# PROC099A_LDO.net
KiCad netlist of a schematic drawn in Altium Designer
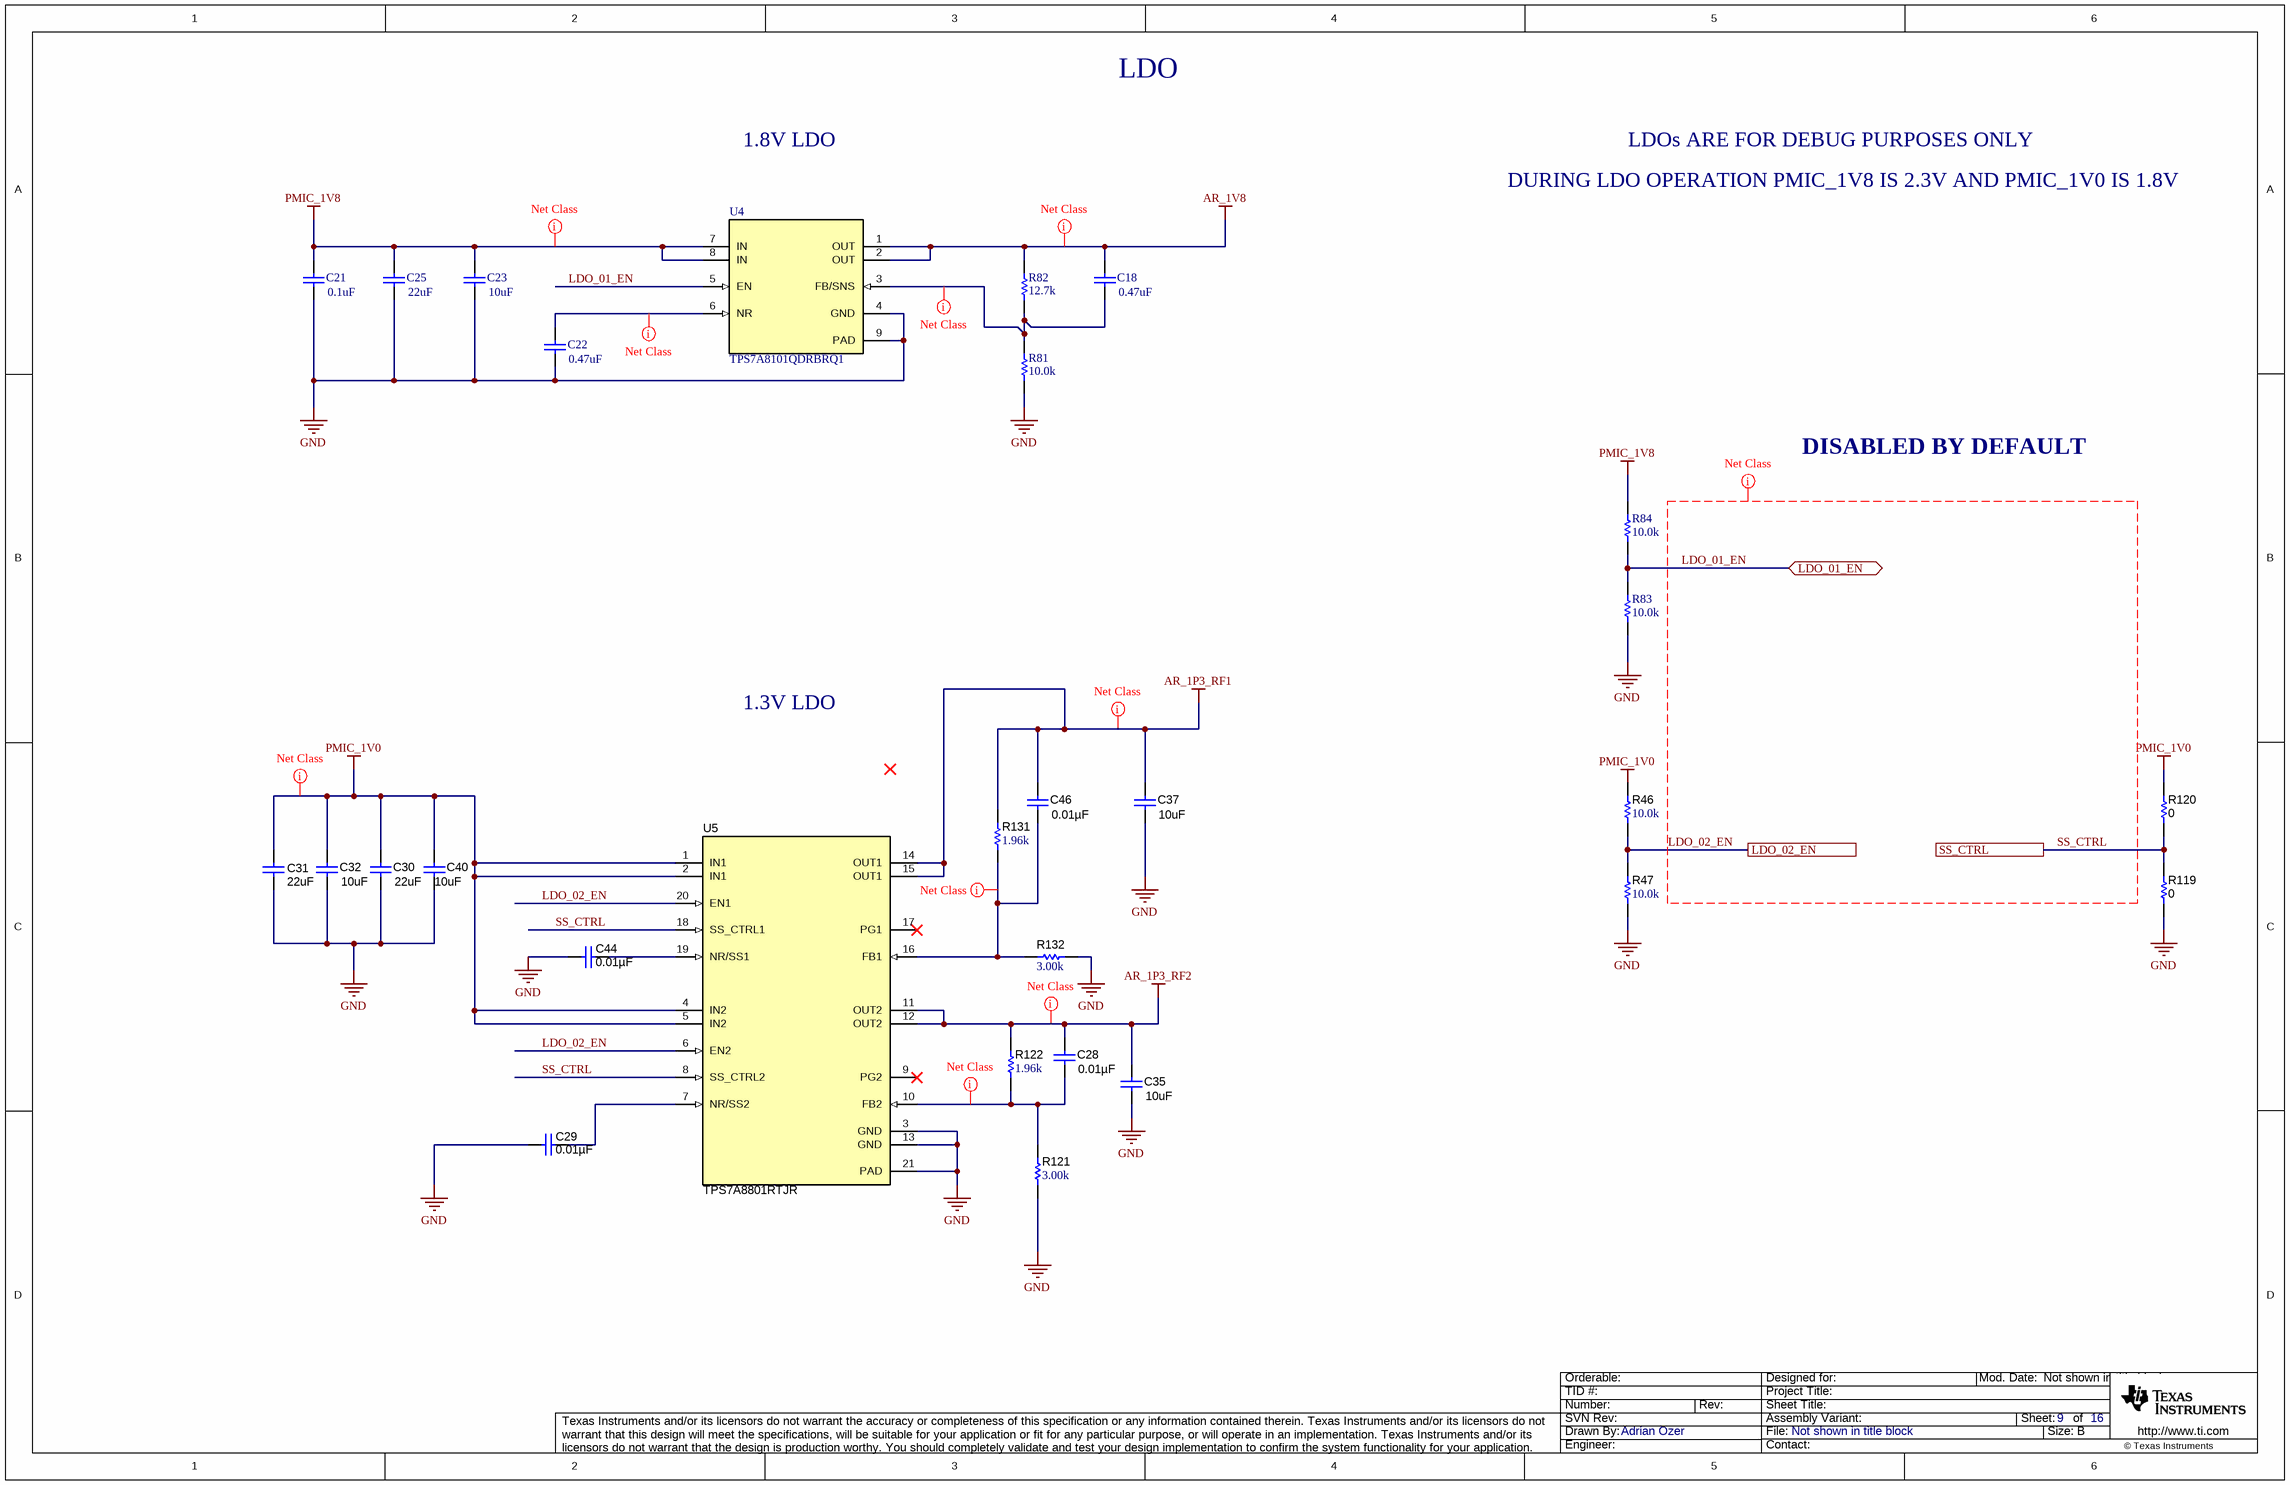
[diagram p0: PROC099A_LDO.SchDoc]

(export (version "E")
  (design (tool "Eeschema 10.0.6"))
  (components
    (comp (ref "C18")
      (value "GCM188R71C474KA55D")
      (footprint "0603")
      (description "CAP, CERM, 0.47 uF, 16 V, +/- 10%, X7R, AEC-Q200 Grade 1, 0603")
      (fields
        (field (name "MANUFACTURER") "MuRata")
        (field (name "VALUEDISPLAYED") "0.47uF")
        (field (name "PUBLISHER") "Texas Instruments")
      )
      (libsource (lib "Altium Vault - TI") (part "Capacitor"))
    )
    (comp (ref "C21")
      (value "CGA2B3X7R1H104K050BB")
      (footprint "0402")
      (description "CAP, CERM, 0.1 uF, 50 V, +/- 10%, X7R, AEC-Q200 Grade 1, 0402")
      (fields
        (field (name "MANUFACTURER") "TDK")
        (field (name "VALUEDISPLAYED") "0.1uF")
        (field (name "PUBLISHER") "Texas Instruments")
      )
      (libsource (lib "Altium Vault - TI") (part "Capacitor"))
    )
    (comp (ref "C22")
      (value "GCM188R71C474KA55D")
      (footprint "0603")
      (description "CAP, CERM, 0.47 uF, 16 V, +/- 10%, X7R, AEC-Q200 Grade 1, 0603")
      (fields
        (field (name "MANUFACTURER") "MuRata")
        (field (name "VALUEDISPLAYED") "0.47uF")
        (field (name "PUBLISHER") "Texas Instruments")
      )
      (libsource (lib "Altium Vault - TI") (part "Capacitor"))
    )
    (comp (ref "C23")
      (value "GCM21BR71A106KE22L")
      (footprint "0805_HV")
      (description "CAP, CERM, 10 uF, 10 V, +/- 10%, X7R, 0805")
      (fields
        (field (name "MANUFACTURER") "MuRata")
        (field (name "VALUEDISPLAYED") "10uF")
        (field (name "PUBLISHER") "Texas Instruments")
      )
      (libsource (lib "Altium Vault - TI") (part "Capacitor"))
    )
    (comp (ref "C25")
      (value "CGA5L1X7R0J226M160AC")
      (footprint "1206_180")
      (description "CAP, CERM, 22 uF, 6.3 V, +/- 10%, X7R, AEC-Q200 Grade 1, 1206")
      (fields
        (field (name "MANUFACTURER") "TDK")
        (field (name "VALUEDISPLAYED") "22uF")
        (field (name "PUBLISHER") "Texas Instruments")
      )
      (libsource (lib "Altium Vault - TI") (part "Capacitor"))
    )
    (comp (ref "C28")
      (value "CGA2B3X8R1H103K050BB")
      (footprint "0402L")
      (description "CAP, CERM, 0.01 µF, 50 V,+/- 10%, X8R, AEC-Q200 Grade 0, 0402")
      (fields (field (name "MANUFACTURER") "TDK") (field (name "VALUEDISPLAYED") "0.01µF"))
      (libsource (lib "Altium Vault - TI") (part "Capacitor"))
    )
    (comp (ref "C29")
      (value "CGA2B3X8R1H103K050BB")
      (footprint "0402L")
      (description "CAP, CERM, 0.01 µF, 50 V,+/- 10%, X8R, AEC-Q200 Grade 0, 0402")
      (fields (field (name "MANUFACTURER") "TDK") (field (name "VALUEDISPLAYED") "0.01µF"))
      (libsource (lib "Altium Vault - TI") (part "Capacitor"))
    )
    (comp (ref "C30")
      (value "CGA5L1X7R0J226M160AC")
      (footprint "1206_180")
      (description "CAP, CERM, 22 uF, 6.3 V, +/- 10%, X7R, AEC-Q200 Grade 1, 1206")
      (fields
        (field (name "MANUFACTURER") "TDK")
        (field (name "VALUEDISPLAYED") "22uF")
        (field (name "PUBLISHER") "Texas Instruments")
      )
      (libsource (lib "Altium Vault - TI") (part "Capacitor"))
    )
    (comp (ref "C31")
      (value "CGA5L1X7R0J226M160AC")
      (footprint "1206_180")
      (description "CAP, CERM, 22 uF, 6.3 V, +/- 10%, X7R, AEC-Q200 Grade 1, 1206")
      (fields
        (field (name "MANUFACTURER") "TDK")
        (field (name "VALUEDISPLAYED") "22uF")
        (field (name "PUBLISHER") "Texas Instruments")
      )
      (libsource (lib "Altium Vault - TI") (part "Capacitor"))
    )
    (comp (ref "C32")
      (value "GCM21BR71A106KE22L")
      (footprint "0805")
      (description "CAP, CERM, 10 uF, 10 V, +/- 10%, X7R, 0805")
      (fields
        (field (name "MANUFACTURER") "MuRata")
        (field (name "VALUEDISPLAYED") "10uF")
        (field (name "PUBLISHER") "Texas Instruments")
      )
      (libsource (lib "Altium Vault - TI") (part "CMP-0008017-2"))
    )
    (comp (ref "C35")
      (value "GCM21BR71A106KE22L")
      (footprint "0805_HV")
      (description "CAP, CERM, 10 uF, 10 V, +/- 10%, X7R, 0805")
      (fields
        (field (name "MANUFACTURER") "MuRata")
        (field (name "VALUEDISPLAYED") "10uF")
        (field (name "PUBLISHER") "Texas Instruments")
      )
      (libsource (lib "Altium Vault - TI") (part "CMP-0008017-2"))
    )
    (comp (ref "C37")
      (value "GCM21BR71A106KE22L")
      (footprint "0805_HV")
      (description "CAP, CERM, 10 uF, 10 V, +/- 10%, X7R, 0805")
      (fields
        (field (name "MANUFACTURER") "MuRata")
        (field (name "VALUEDISPLAYED") "10uF")
        (field (name "PUBLISHER") "Texas Instruments")
      )
      (libsource (lib "Altium Vault - TI") (part "CMP-0008017-2"))
    )
    (comp (ref "C40")
      (value "GCM21BR71A106KE22L")
      (footprint "0805_HV1")
      (description "CAP, CERM, 10 uF, 10 V, +/- 10%, X7R, 0805")
      (fields
        (field (name "MANUFACTURER") "MuRata")
        (field (name "VALUEDISPLAYED") "10uF")
        (field (name "PUBLISHER") "Texas Instruments")
      )
      (libsource (lib "Altium Vault - TI") (part "CMP-0008017-2"))
    )
    (comp (ref "C44")
      (value "CGA2B3X8R1H103K050BB")
      (footprint "0402L")
      (description "CAP, CERM, 0.01 µF, 50 V,+/- 10%, X8R, AEC-Q200 Grade 0, 0402")
      (fields (field (name "MANUFACTURER") "TDK") (field (name "VALUEDISPLAYED") "0.01µF"))
      (libsource (lib "Altium Vault - TI") (part "Capacitor"))
    )
    (comp (ref "C46")
      (value "CGA2B3X8R1H103K050BB")
      (footprint "0402L")
      (description "CAP, CERM, 0.01 µF, 50 V,+/- 10%, X8R, AEC-Q200 Grade 0, 0402")
      (fields (field (name "MANUFACTURER") "TDK") (field (name "VALUEDISPLAYED") "0.01µF"))
      (libsource (lib "Altium Vault - TI") (part "Capacitor"))
    )
    (comp (ref "R46")
      (value "CRCW040210K0FKED")
      (footprint "0402L")
      (description "RES, 10.0 k, 1%, 0.063 W, AEC-Q200 Grade 0, 0402")
      (fields (field (name "MANUFACTURER") "Vishay-Dale") (field (name "VALUEDISPLAYED") "10.0k"))
      (libsource (lib "Altium Vault - TI") (part "Resistor"))
    )
    (comp (ref "R47")
      (value "CRCW040210K0FKED")
      (footprint "0402L")
      (description "RES, 10.0 k, 1%, 0.063 W, AEC-Q200 Grade 0, 0402")
      (fields (field (name "MANUFACTURER") "Vishay-Dale") (field (name "VALUEDISPLAYED") "10.0k"))
      (libsource (lib "Altium Vault - TI") (part "Resistor"))
    )
    (comp (ref "R81")
      (value "CRCW040210K0FKED")
      (footprint "0402L")
      (description "RES, 10.0 k, 1%, 0.063 W, AEC-Q200 Grade 0, 0402")
      (fields (field (name "MANUFACTURER") "Vishay-Dale") (field (name "VALUEDISPLAYED") "10.0k"))
      (libsource (lib "Altium Vault - TI") (part "CMP-0025958-3"))
    )
    (comp (ref "R82")
      (value "CRCW040212K7FKED")
      (footprint "0402L")
      (description "RES, 12.7 k, 1%, 0.063 W, AEC-Q200 Grade 0, 0402")
      (fields (field (name "MANUFACTURER") "Vishay-Dale") (field (name "VALUEDISPLAYED") "12.7k"))
      (libsource (lib "Altium Vault - TI") (part "CMP-0025993-3"))
    )
    (comp (ref "R83")
      (value "CRCW040210K0FKED")
      (footprint "0402")
      (description "RES, 10.0 k, 1%, 0.063 W, AEC-Q200 Grade 0, 0402")
      (fields (field (name "MANUFACTURER") "Vishay-Dale") (field (name "VALUEDISPLAYED") "10.0k"))
      (libsource (lib "Altium Vault - TI") (part "Resistor"))
    )
    (comp (ref "R84")
      (value "CRCW040210K0FKED")
      (footprint "0402")
      (description "RES, 10.0 k, 1%, 0.063 W, AEC-Q200 Grade 0, 0402")
      (fields (field (name "MANUFACTURER") "Vishay-Dale") (field (name "VALUEDISPLAYED") "10.0k"))
      (libsource (lib "Altium Vault - TI") (part "Resistor"))
    )
    (comp (ref "R119")
      (value "ERJ-2GE0R00X")
      (footprint "0402L")
      (description "RES, 0, 5%, 0.063 W, 0402")
      (fields
        (field (name "MANUFACTURER") "Panasonic")
        (field (name "VALUEDISPLAYED") "0")
        (field (name "PUBLISHER") "Texas Instruments")
      )
      (libsource (lib "Altium Vault - TI") (part "Resistor"))
    )
    (comp (ref "R120")
      (value "ERJ-2GE0R00X")
      (footprint "0402L")
      (description "RES, 0, 5%, 0.063 W, 0402")
      (fields
        (field (name "MANUFACTURER") "Panasonic")
        (field (name "VALUEDISPLAYED") "0")
        (field (name "PUBLISHER") "Texas Instruments")
      )
      (libsource (lib "Altium Vault - TI") (part "CMP-0026992-2"))
    )
    (comp (ref "R121")
      (value "CRCW04023K00FKED")
      (footprint "0402L")
      (description "RES, 3.00 k, 1%, 0.063 W, AEC-Q200 Grade 0, 0402")
      (fields (field (name "MANUFACTURER") "Vishay-Dale") (field (name "VALUEDISPLAYED") "3.00k"))
      (libsource (lib "Altium Vault - TI") (part "Resistor"))
    )
    (comp (ref "R122")
      (value "CRCW04021K96FKED")
      (footprint "0402L")
      (description "RES, 1.96 k, 1%, 0.063 W, AEC-Q200 Grade 0, 0402")
      (fields (field (name "MANUFACTURER") "Vishay-Dale") (field (name "VALUEDISPLAYED") "1.96k"))
      (libsource (lib "Altium Vault - TI") (part "Resistor"))
    )
    (comp (ref "R131")
      (value "CRCW04021K96FKED")
      (footprint "0402L")
      (description "RES, 1.96 k, 1%, 0.063 W, AEC-Q200 Grade 0, 0402")
      (fields (field (name "MANUFACTURER") "Vishay-Dale") (field (name "VALUEDISPLAYED") "1.96k"))
      (libsource (lib "Altium Vault - TI") (part "Resistor"))
    )
    (comp (ref "R132")
      (value "CRCW04023K00FKED")
      (footprint "0402L")
      (description "RES, 3.00 k, 1%, 0.063 W, AEC-Q200 Grade 0, 0402")
      (fields (field (name "MANUFACTURER") "Vishay-Dale") (field (name "VALUEDISPLAYED") "3.00k"))
      (libsource (lib "Altium Vault - TI") (part "Resistor"))
    )
    (comp (ref "U4")
      (value "TPS7A8101QDRBRQ1")
      (footprint "DRB0008A")
      (fields
        (field (name "MANUFACTURER") "Texas Instruments")
        (field (name "PARTNUMBER") "TPS7A8101QDRBRQ1")
        (field (name "PUBLISHER") "Texas Instruments")
      )
      (libsource (lib "Altium Vault - TI") (part "TPS7A80xx"))
    )
    (comp (ref "U5")
      (value "TPS7A8801RTJR")
      (footprint "RTJ0020D")
      (description "Dual, 1-A, Low Noise (3.8-uVRMS), LDO Voltage Regulator, RTJ0020D (WQFN-20)")
      (fields
        (field (name "ALTERNATE PARTNUMBER") "TPS7A8801RTJT")
        (field (name "MANUFACTURER") "Texas Instruments")
        (field (name "PARTNUMBER") "TPS7A8801RTJR")
        (field (name "PUBLISHER") "Texas Instruments")
      )
      (libsource (lib "Altium Vault - TI") (part "TPS7A8801"))
    )
  )
  (nets
    (net (code "1") (name "/LDO_01_EN") (class "Default")
      (node (ref "R83") (pin "2") (pinfunction "2_2") (pintype "passive"))
      (node (ref "R84") (pin "1") (pinfunction "1_1") (pintype "passive"))
      (node (ref "U4") (pin "5") (pinfunction "EN_5") (pintype "input"))
    )
    (net (code "2") (name "/LDO_02_EN") (class "Default")
      (node (ref "R46") (pin "2") (pinfunction "2_2") (pintype "passive"))
      (node (ref "R47") (pin "1") (pinfunction "1_1") (pintype "passive"))
      (node (ref "U5") (pin "20") (pinfunction "EN1_20") (pintype "input"))
      (node (ref "U5") (pin "6") (pinfunction "EN2_6") (pintype "input"))
    )
    (net (code "3") (name "/SS_CTRL") (class "Default")
      (node (ref "R119") (pin "2") (pinfunction "2_2") (pintype "passive"))
      (node (ref "R120") (pin "1") (pinfunction "1_1") (pintype "passive"))
      (node (ref "U5") (pin "18") (pinfunction "SS_CTRL1_18") (pintype "input"))
      (node (ref "U5") (pin "8") (pinfunction "SS_CTRL2_8") (pintype "input"))
    )
    (net (code "4") (name "AR_1P3_RF1") (class "Default")
      (node (ref "C37") (pin "2") (pinfunction "2_2") (pintype "passive"))
      (node (ref "C46") (pin "2") (pinfunction "2_2") (pintype "passive"))
      (node (ref "R131") (pin "2") (pinfunction "2_2") (pintype "passive"))
      (node (ref "U5") (pin "14") (pinfunction "OUT1_14") (pintype "power_in"))
      (node (ref "U5") (pin "15") (pinfunction "OUT1_15") (pintype "power_in"))
    )
    (net (code "5") (name "AR_1P3_RF2") (class "Default")
      (node (ref "C28") (pin "2") (pinfunction "2_2") (pintype "passive"))
      (node (ref "C35") (pin "2") (pinfunction "2_2") (pintype "passive"))
      (node (ref "R122") (pin "2") (pinfunction "2_2") (pintype "passive"))
      (node (ref "U5") (pin "11") (pinfunction "OUT2_11") (pintype "power_in"))
      (node (ref "U5") (pin "12") (pinfunction "OUT2_12") (pintype "power_in"))
    )
    (net (code "6") (name "AR_1V8") (class "Default")
      (node (ref "C18") (pin "1") (pinfunction "1_1") (pintype "passive"))
      (node (ref "R82") (pin "2") (pinfunction "2_2") (pintype "passive"))
      (node (ref "U4") (pin "1") (pinfunction "OUT_1") (pintype "power_in"))
      (node (ref "U4") (pin "2") (pinfunction "OUT_2") (pintype "power_in"))
    )
    (net (code "7") (name "GND") (class "Default")
      (node (ref "C21") (pin "2") (pinfunction "2_2") (pintype "passive"))
      (node (ref "C22") (pin "2") (pinfunction "2_2") (pintype "passive"))
      (node (ref "C23") (pin "2") (pinfunction "2_2") (pintype "passive"))
      (node (ref "C25") (pin "2") (pinfunction "2_2") (pintype "passive"))
      (node (ref "C29") (pin "1") (pinfunction "1_1") (pintype "passive"))
      (node (ref "C30") (pin "1") (pinfunction "1_1") (pintype "passive"))
      (node (ref "C31") (pin "1") (pinfunction "1_1") (pintype "passive"))
      (node (ref "C32") (pin "1") (pinfunction "1_1") (pintype "passive"))
      (node (ref "C35") (pin "1") (pinfunction "1_1") (pintype "passive"))
      (node (ref "C37") (pin "1") (pinfunction "1_1") (pintype "passive"))
      (node (ref "C40") (pin "1") (pinfunction "1_1") (pintype "passive"))
      (node (ref "C44") (pin "1") (pinfunction "1_1") (pintype "passive"))
      (node (ref "R119") (pin "1") (pinfunction "1_1") (pintype "passive"))
      (node (ref "R121") (pin "1") (pinfunction "1_1") (pintype "passive"))
      (node (ref "R132") (pin "1") (pinfunction "1_1") (pintype "passive"))
      (node (ref "R47") (pin "2") (pinfunction "2_2") (pintype "passive"))
      (node (ref "R81") (pin "1") (pinfunction "1_1") (pintype "passive"))
      (node (ref "R83") (pin "1") (pinfunction "1_1") (pintype "passive"))
      (node (ref "U4") (pin "4") (pinfunction "GND_4") (pintype "power_in"))
      (node (ref "U4") (pin "9") (pinfunction "PAD_9") (pintype "passive"))
      (node (ref "U5") (pin "13") (pinfunction "GND_13") (pintype "power_in"))
      (node (ref "U5") (pin "21") (pinfunction "PAD_21") (pintype "power_in"))
      (node (ref "U5") (pin "3") (pinfunction "GND_3") (pintype "power_in"))
    )
    (net (code "8") (name "Net-(U4-FB{slash}SNS)") (class "Default")
      (node (ref "C18") (pin "2") (pinfunction "2_2") (pintype "passive"))
      (node (ref "R81") (pin "2") (pinfunction "2_2") (pintype "passive"))
      (node (ref "R82") (pin "1") (pinfunction "1_1") (pintype "passive"))
      (node (ref "U4") (pin "3") (pinfunction "FB/SNS_3") (pintype "input"))
    )
    (net (code "9") (name "Net-(U4-NR)") (class "Default")
      (node (ref "C22") (pin "1") (pinfunction "1_1") (pintype "passive"))
      (node (ref "U4") (pin "6") (pinfunction "NR_6") (pintype "input"))
    )
    (net (code "10") (name "Net-(U5-FB1)") (class "Default")
      (node (ref "C46") (pin "1") (pinfunction "1_1") (pintype "passive"))
      (node (ref "R131") (pin "1") (pinfunction "1_1") (pintype "passive"))
      (node (ref "R132") (pin "2") (pinfunction "2_2") (pintype "passive"))
      (node (ref "U5") (pin "16") (pinfunction "FB1_16") (pintype "input"))
    )
    (net (code "11") (name "Net-(U5-FB2)") (class "Default")
      (node (ref "C28") (pin "1") (pinfunction "1_1") (pintype "passive"))
      (node (ref "R121") (pin "2") (pinfunction "2_2") (pintype "passive"))
      (node (ref "R122") (pin "1") (pinfunction "1_1") (pintype "passive"))
      (node (ref "U5") (pin "10") (pinfunction "FB2_10") (pintype "input"))
    )
    (net (code "12") (name "Net-(U5-NR{slash}SS1)") (class "Default")
      (node (ref "C44") (pin "2") (pinfunction "2_2") (pintype "passive"))
      (node (ref "U5") (pin "19") (pinfunction "NR/SS1_19") (pintype "input"))
    )
    (net (code "13") (name "Net-(U5-NR{slash}SS2)") (class "Default")
      (node (ref "C29") (pin "2") (pinfunction "2_2") (pintype "passive"))
      (node (ref "U5") (pin "7") (pinfunction "NR/SS2_7") (pintype "input"))
    )
    (net (code "14") (name "PMIC_1V0") (class "Default")
      (node (ref "C30") (pin "2") (pinfunction "2_2") (pintype "passive"))
      (node (ref "C31") (pin "2") (pinfunction "2_2") (pintype "passive"))
      (node (ref "C32") (pin "2") (pinfunction "2_2") (pintype "passive"))
      (node (ref "C40") (pin "2") (pinfunction "2_2") (pintype "passive"))
      (node (ref "R120") (pin "2") (pinfunction "2_2") (pintype "passive"))
      (node (ref "R46") (pin "1") (pinfunction "1_1") (pintype "passive"))
      (node (ref "U5") (pin "1") (pinfunction "IN1_1") (pintype "power_in"))
      (node (ref "U5") (pin "2") (pinfunction "IN1_2") (pintype "power_in"))
      (node (ref "U5") (pin "4") (pinfunction "IN2_4") (pintype "power_in"))
      (node (ref "U5") (pin "5") (pinfunction "IN2_5") (pintype "power_in"))
    )
    (net (code "15") (name "PMIC_1V8") (class "Default")
      (node (ref "C21") (pin "1") (pinfunction "1_1") (pintype "passive"))
      (node (ref "C23") (pin "1") (pinfunction "1_1") (pintype "passive"))
      (node (ref "C25") (pin "1") (pinfunction "1_1") (pintype "passive"))
      (node (ref "R84") (pin "2") (pinfunction "2_2") (pintype "passive"))
      (node (ref "U4") (pin "7") (pinfunction "IN_7") (pintype "power_in"))
      (node (ref "U4") (pin "8") (pinfunction "IN_8") (pintype "power_in"))
    )
    (net (code "16") (name "unconnected-(U5-PG1-Pad17)") (class "Default")
      (node (ref "U5") (pin "17") (pinfunction "PG1_17") (pintype "open_collector+no_connect"))
    )
    (net (code "17") (name "unconnected-(U5-PG2-Pad9)") (class "Default")
      (node (ref "U5") (pin "9") (pinfunction "PG2_9") (pintype "open_collector+no_connect"))
    )
  )
)
